# Inverter_Power.net
KiCad netlist of a schematic drawn in Altium Designer
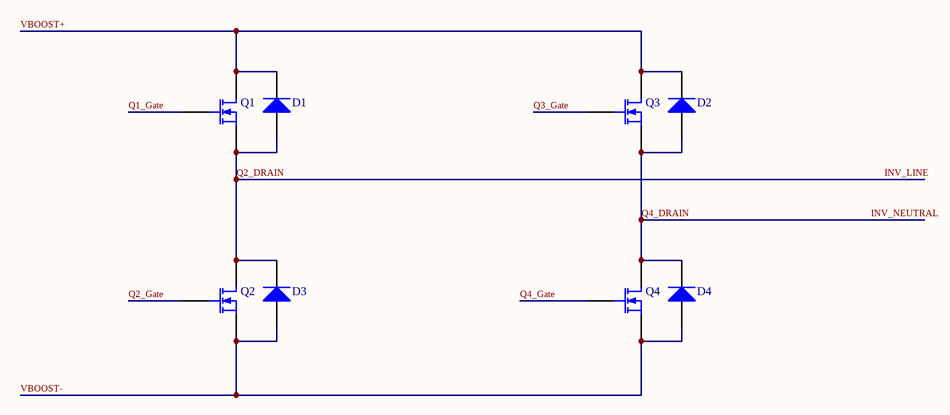
[diagram p0: Inverter_Power.SchDoc]

(export (version "E")
  (design (tool "Eeschema 10.0.6"))
  (components
    (comp (ref "D1")
      (value "Diode")
      (footprint "SMC")
      (description "Default Diode")
      (fields (field (name "PUBLISHER") "Altium Limited"))
      (libsource (lib "Miscellaneous Devices") (part "Diode"))
    )
    (comp (ref "D2")
      (value "Diode")
      (footprint "SMC")
      (description "Default Diode")
      (fields (field (name "PUBLISHER") "Altium Limited"))
      (libsource (lib "Miscellaneous Devices") (part "Diode"))
    )
    (comp (ref "D3")
      (value "Diode")
      (footprint "SMC")
      (description "Default Diode")
      (fields (field (name "PUBLISHER") "Altium Limited"))
      (libsource (lib "Miscellaneous Devices") (part "Diode"))
    )
    (comp (ref "D4")
      (value "Diode")
      (footprint "SMC")
      (description "Default Diode")
      (fields (field (name "PUBLISHER") "Altium Limited"))
      (libsource (lib "Miscellaneous Devices") (part "Diode"))
    )
    (comp (ref "Q1")
      (value "MOSFET-N")
      (footprint "E3")
      (description "N-Channel MOSFET")
      (fields (field (name "PUBLISHER") "Altium Limited"))
      (libsource (lib "Miscellaneous Devices") (part "MOSFET-N"))
    )
    (comp (ref "Q2")
      (value "MOSFET-N")
      (footprint "E3")
      (description "N-Channel MOSFET")
      (fields (field (name "PUBLISHER") "Altium Limited"))
      (libsource (lib "Miscellaneous Devices") (part "MOSFET-N"))
    )
    (comp (ref "Q3")
      (value "MOSFET-N")
      (footprint "E3")
      (description "N-Channel MOSFET")
      (fields (field (name "PUBLISHER") "Altium Limited"))
      (libsource (lib "Miscellaneous Devices") (part "MOSFET-N"))
    )
    (comp (ref "Q4")
      (value "MOSFET-N")
      (footprint "E3")
      (description "N-Channel MOSFET")
      (fields (field (name "PUBLISHER") "Altium Limited"))
      (libsource (lib "Miscellaneous Devices") (part "MOSFET-N"))
    )
  )
  (nets
    (net (code "1") (name "/INV_LINE") (class "Default")
      (node (ref "D1") (pin "1") (pinfunction "A_1") (pintype "passive"))
      (node (ref "D3") (pin "2") (pinfunction "K_2") (pintype "passive"))
      (node (ref "Q1") (pin "3") (pinfunction "S_3") (pintype "passive"))
      (node (ref "Q2") (pin "1") (pinfunction "D_1") (pintype "passive"))
    )
    (net (code "2") (name "/INV_NEUTRAL") (class "Default")
      (node (ref "D2") (pin "1") (pinfunction "A_1") (pintype "passive"))
      (node (ref "D4") (pin "2") (pinfunction "K_2") (pintype "passive"))
      (node (ref "Q3") (pin "3") (pinfunction "S_3") (pintype "passive"))
      (node (ref "Q4") (pin "1") (pinfunction "D_1") (pintype "passive"))
    )
    (net (code "3") (name "/Q1_Gate") (class "Default")
      (node (ref "Q1") (pin "2") (pinfunction "G_2") (pintype "passive"))
    )
    (net (code "4") (name "/Q2_Gate") (class "Default")
      (node (ref "Q2") (pin "2") (pinfunction "G_2") (pintype "passive"))
    )
    (net (code "5") (name "/Q3_Gate") (class "Default")
      (node (ref "Q3") (pin "2") (pinfunction "G_2") (pintype "passive"))
    )
    (net (code "6") (name "/Q4_Gate") (class "Default")
      (node (ref "Q4") (pin "2") (pinfunction "G_2") (pintype "passive"))
    )
    (net (code "7") (name "/VBOOST+") (class "Default")
      (node (ref "D1") (pin "2") (pinfunction "K_2") (pintype "passive"))
      (node (ref "D2") (pin "2") (pinfunction "K_2") (pintype "passive"))
      (node (ref "Q1") (pin "1") (pinfunction "D_1") (pintype "passive"))
      (node (ref "Q3") (pin "1") (pinfunction "D_1") (pintype "passive"))
    )
    (net (code "8") (name "/VBOOST-") (class "Default")
      (node (ref "D3") (pin "1") (pinfunction "A_1") (pintype "passive"))
      (node (ref "D4") (pin "1") (pinfunction "A_1") (pintype "passive"))
      (node (ref "Q2") (pin "3") (pinfunction "S_3") (pintype "passive"))
      (node (ref "Q4") (pin "3") (pinfunction "S_3") (pintype "passive"))
    )
  )
)
